# Pilot_Interface_005.net
KiCad netlist of a schematic drawn in EAGLE
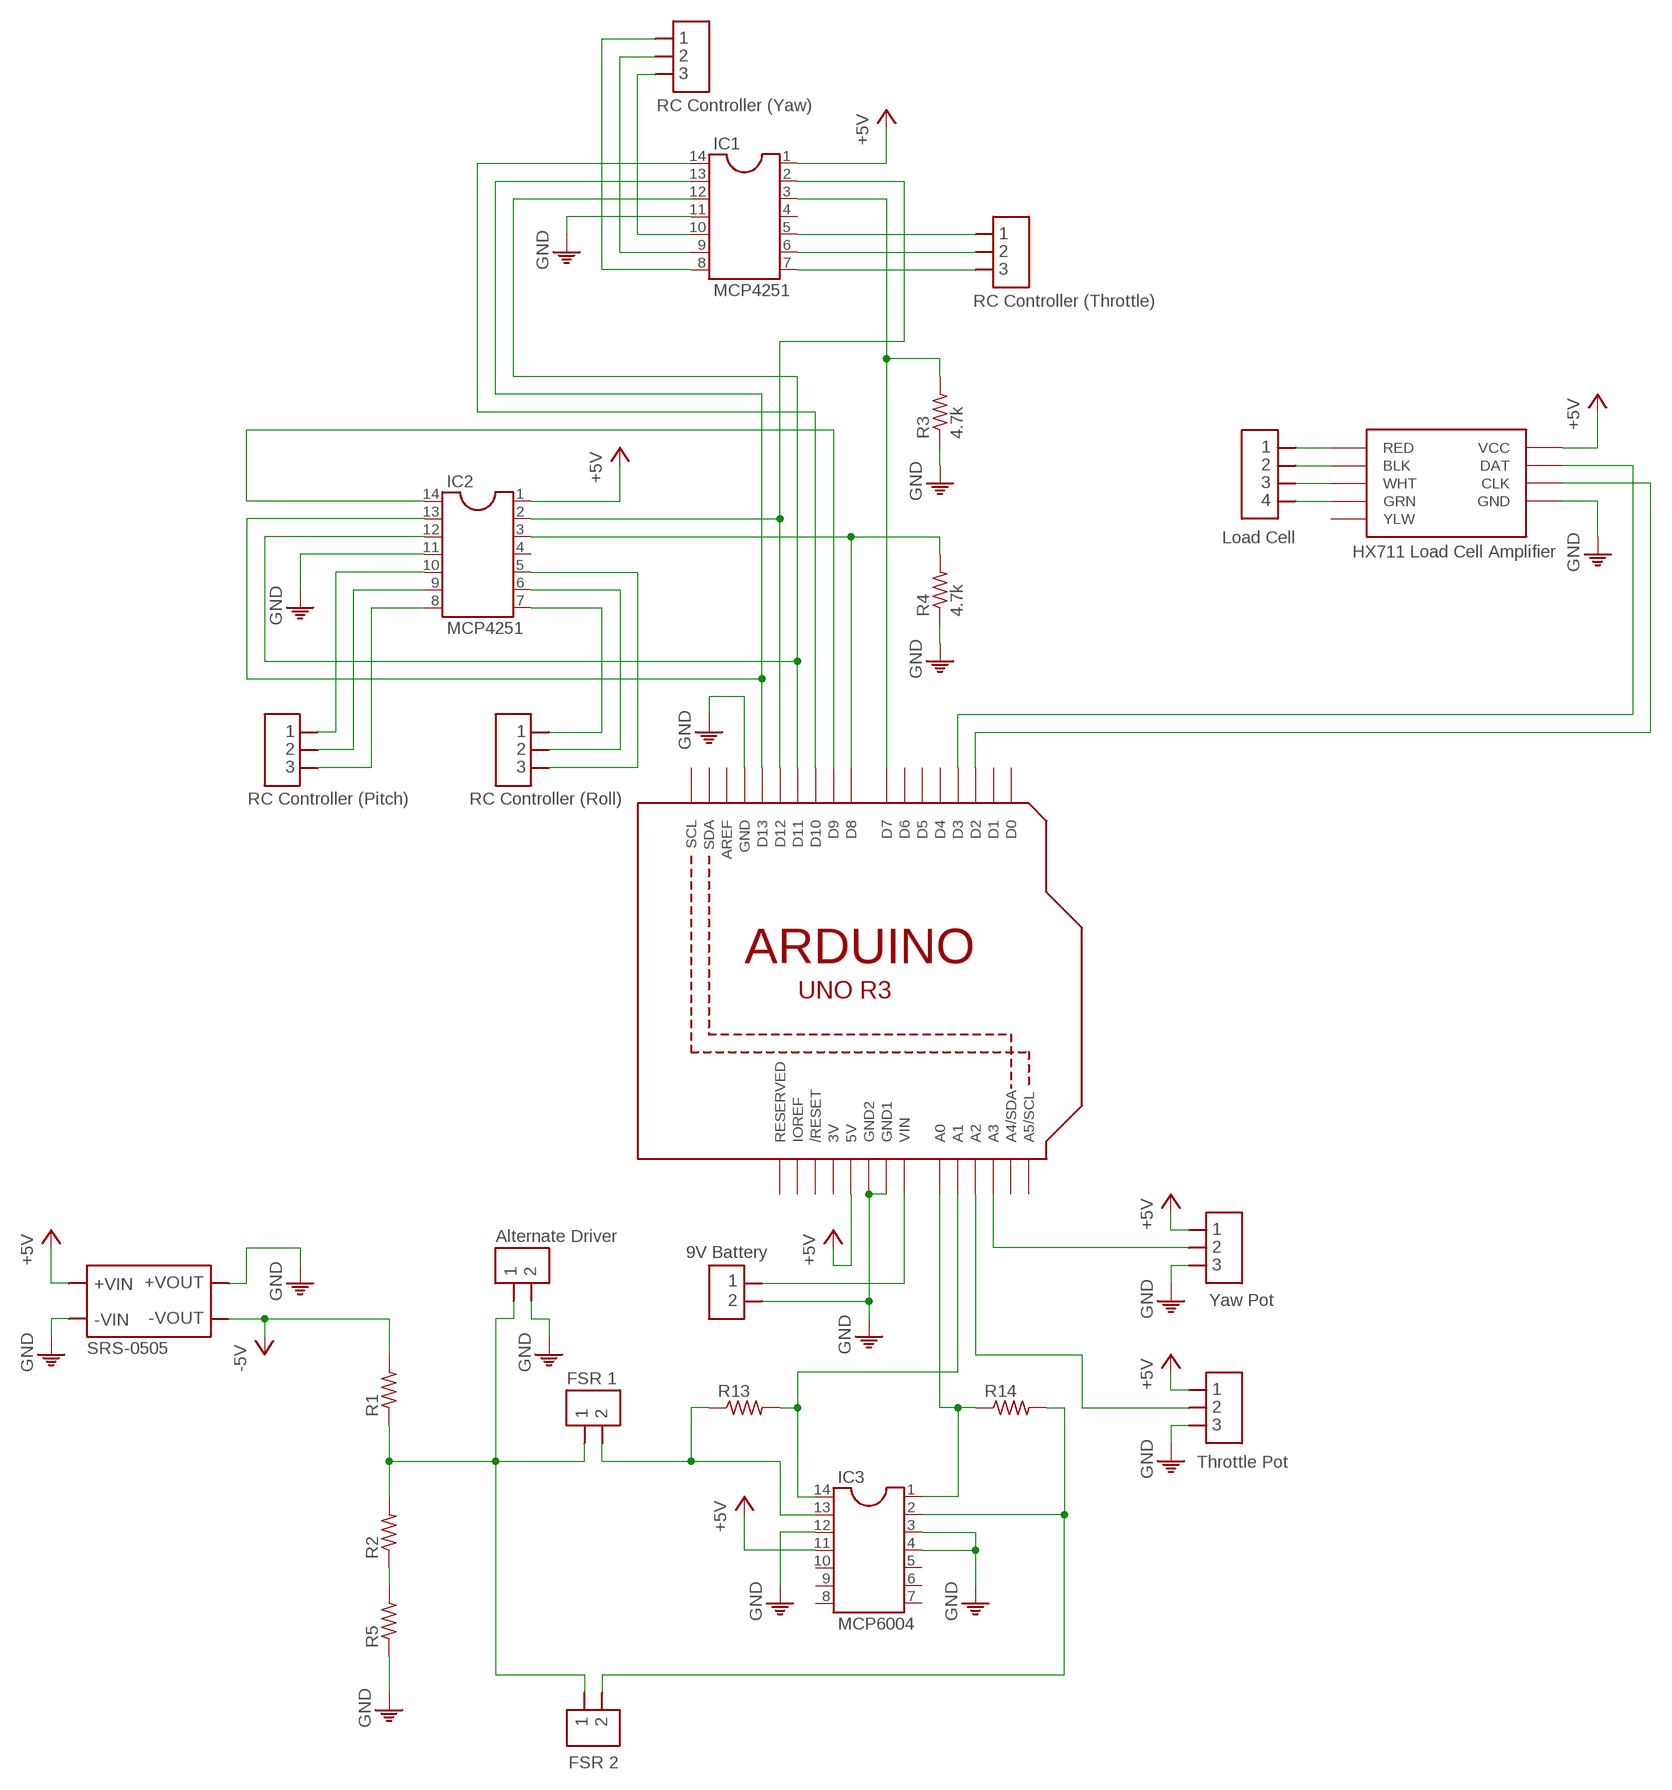
[diagram p0: schematic, sheet 1]

(export (version "E")
  (design (tool "Eeschema 10.0.6"))
  (components
    (comp (ref "IC1")
      (value "MCP4251")
      (footprint "eagle-import:DIL14")
      (libsource (lib "eagle-import") (part "DIL14"))
    )
    (comp (ref "IC2")
      (value "MCP4251")
      (footprint "eagle-import:DIL14")
      (libsource (lib "eagle-import") (part "DIL14"))
    )
    (comp (ref "IC3")
      (value "MCP6004")
      (footprint "eagle-import:DIL14")
      (libsource (lib "eagle-import") (part "DIL14"))
    )
    (comp (ref "R1")
      (value "R-US_0204/2V")
      (footprint "eagle-import:0204V")
      (libsource (lib "eagle-import") (part "R-US_0204/2V"))
    )
    (comp (ref "R2")
      (value "R-US_0204/2V")
      (footprint "eagle-import:0204V")
      (libsource (lib "eagle-import") (part "R-US_0204/2V"))
    )
    (comp (ref "R3")
      (value "4.7k")
      (footprint "eagle-import:0204V")
      (libsource (lib "eagle-import") (part "R-US_0204/2V"))
    )
    (comp (ref "R4")
      (value "4.7k")
      (footprint "eagle-import:0204V")
      (libsource (lib "eagle-import") (part "R-US_0204/2V"))
    )
    (comp (ref "R5")
      (value "R-US_0204/2V")
      (footprint "eagle-import:0204V")
      (libsource (lib "eagle-import") (part "R-US_0204/2V"))
    )
    (comp (ref "R13")
      (value "R-US_0204/2V")
      (footprint "eagle-import:0204V")
      (libsource (lib "eagle-import") (part "R-US_0204/2V"))
    )
    (comp (ref "R14")
      (value "R-US_0204/2V")
      (footprint "eagle-import:0204V")
      (libsource (lib "eagle-import") (part "R-US_0204/2V"))
    )
    (comp (ref "U$1")
      (value "HX711")
      (footprint "eagle-import:HX711")
      (libsource (lib "eagle-import") (part "HX711"))
    )
    (comp (ref "U$2")
      (value "PAD_3")
      (footprint "eagle-import:PAD_3")
      (libsource (lib "eagle-import") (part "PAD_3"))
    )
    (comp (ref "U$3")
      (value "PAD_3")
      (footprint "eagle-import:PAD_3")
      (libsource (lib "eagle-import") (part "PAD_3"))
    )
    (comp (ref "U$4")
      (value "PAD_2")
      (footprint "eagle-import:PAD_2")
      (libsource (lib "eagle-import") (part "PAD_2"))
    )
    (comp (ref "U$5")
      (value "PAD_2")
      (footprint "eagle-import:PAD_2")
      (libsource (lib "eagle-import") (part "PAD_2"))
    )
    (comp (ref "U$6")
      (value "PAD_3")
      (footprint "eagle-import:PAD_3")
      (libsource (lib "eagle-import") (part "PAD_3"))
    )
    (comp (ref "U$7")
      (value "PAD_3")
      (footprint "eagle-import:PAD_3")
      (libsource (lib "eagle-import") (part "PAD_3"))
    )
    (comp (ref "U$8")
      (value "PAD_4")
      (footprint "eagle-import:PAD_4")
      (libsource (lib "eagle-import") (part "PAD_4"))
    )
    (comp (ref "U$9")
      (value "SRS-0505")
      (footprint "eagle-import:SRS-0505")
      (libsource (lib "eagle-import") (part "SRS-0505"))
    )
    (comp (ref "U$10")
      (value "PAD_3")
      (footprint "eagle-import:PAD_3")
      (libsource (lib "eagle-import") (part "PAD_3"))
    )
    (comp (ref "U$11")
      (value "PAD_3")
      (footprint "eagle-import:PAD_3")
      (libsource (lib "eagle-import") (part "PAD_3"))
    )
    (comp (ref "U$12")
      (value "PAD_2")
      (footprint "eagle-import:PAD_2")
      (libsource (lib "eagle-import") (part "PAD_2"))
    )
    (comp (ref "U$13")
      (value "PAD_2")
      (footprint "eagle-import:PAD_2")
      (libsource (lib "eagle-import") (part "PAD_2"))
    )
    (comp (ref "U1")
      (value "ARDUINOR3")
      (footprint "eagle-import:ARDUINOR3")
      (libsource (lib "eagle-import") (part "ARDUINOR3"))
    )
  )
  (nets
    (net (code "1") (name "+5V") (class "Default")
      (node (ref "IC1") (pin "1") (pinfunction "14_1") (pintype "passive"))
      (node (ref "IC2") (pin "1") (pinfunction "14_1") (pintype "passive"))
      (node (ref "IC3") (pin "11") (pinfunction "4_11") (pintype "passive"))
      (node (ref "U$1") (pin "VCC") (pinfunction "VCC_VCC") (pintype "bidirectional"))
      (node (ref "U$6") (pin "P$1") (pinfunction "P$1_P$1") (pintype "bidirectional"))
      (node (ref "U$7") (pin "P$1") (pinfunction "P$1_P$1") (pintype "bidirectional"))
      (node (ref "U$9") (pin "P$1") (pinfunction "+VIN_P$1") (pintype "bidirectional"))
      (node (ref "U$9") (pin "P$16") (pinfunction "+VIN_P$16") (pintype "bidirectional"))
      (node (ref "U1") (pin "5V") (pinfunction "5V_5V") (pintype "power_in"))
    )
    (net (code "2") (name "-5V") (class "Default")
      (node (ref "R1") (pin "2") (pinfunction "2_2") (pintype "passive"))
      (node (ref "U$9") (pin "P$11") (pinfunction "-VOUT_P$11") (pintype "bidirectional"))
      (node (ref "U$9") (pin "P$6") (pinfunction "-VOUT_P$6") (pintype "bidirectional"))
    )
    (net (code "3") (name "/3V") (class "Default")
      (node (ref "U1") (pin "3V") (pinfunction "3V_3V") (pintype "power_in"))
    )
    (net (code "4") (name "GND") (class "Default")
      (node (ref "IC1") (pin "11") (pinfunction "4_11") (pintype "passive"))
      (node (ref "IC2") (pin "11") (pinfunction "4_11") (pintype "passive"))
      (node (ref "IC3") (pin "12") (pinfunction "3_12") (pintype "passive"))
      (node (ref "IC3") (pin "3") (pinfunction "12_3") (pintype "passive"))
      (node (ref "IC3") (pin "4") (pinfunction "11_4") (pintype "passive"))
      (node (ref "R3") (pin "1") (pinfunction "1_1") (pintype "passive"))
      (node (ref "R4") (pin "1") (pinfunction "1_1") (pintype "passive"))
      (node (ref "R5") (pin "1") (pinfunction "1_1") (pintype "passive"))
      (node (ref "U$1") (pin "GND") (pinfunction "GND_GND") (pintype "bidirectional"))
      (node (ref "U$12") (pin "P$2") (pinfunction "P$2_P$2") (pintype "bidirectional"))
      (node (ref "U$13") (pin "P$2") (pinfunction "P$2_P$2") (pintype "bidirectional"))
      (node (ref "U$6") (pin "P$3") (pinfunction "P$3_P$3") (pintype "bidirectional"))
      (node (ref "U$7") (pin "P$3") (pinfunction "P$3_P$3") (pintype "bidirectional"))
      (node (ref "U$9") (pin "P$10") (pinfunction "+VOUT_P$10") (pintype "bidirectional"))
      (node (ref "U$9") (pin "P$7") (pinfunction "+VOUT_P$7") (pintype "bidirectional"))
      (node (ref "U$9") (pin "P$8") (pinfunction "-VIN_P$8") (pintype "bidirectional"))
      (node (ref "U$9") (pin "P$9") (pinfunction "-VIN_P$9") (pintype "bidirectional"))
      (node (ref "U1") (pin "GND") (pinfunction "GND_GND") (pintype "power_in"))
      (node (ref "U1") (pin "GND1") (pinfunction "GND1_GND1") (pintype "power_in"))
      (node (ref "U1") (pin "GND2") (pinfunction "GND2_GND2") (pintype "power_in"))
    )
    (net (code "5") (name "Net-(IC1-1)") (class "Default")
      (node (ref "IC1") (pin "14") (pinfunction "1_14") (pintype "passive"))
      (node (ref "U1") (pin "D10") (pinfunction "D10_D10") (pintype "bidirectional"))
    )
    (net (code "6") (name "Net-(IC1-2)") (class "Default")
      (node (ref "IC1") (pin "13") (pinfunction "2_13") (pintype "passive"))
      (node (ref "IC2") (pin "13") (pinfunction "2_13") (pintype "passive"))
      (node (ref "U1") (pin "D13") (pinfunction "D13_D13") (pintype "bidirectional"))
    )
    (net (code "7") (name "Net-(IC1-3)") (class "Default")
      (node (ref "IC1") (pin "12") (pinfunction "3_12") (pintype "passive"))
      (node (ref "IC2") (pin "12") (pinfunction "3_12") (pintype "passive"))
      (node (ref "U1") (pin "D11") (pinfunction "D11_D11") (pintype "bidirectional"))
    )
    (net (code "8") (name "Net-(IC1-5)") (class "Default")
      (node (ref "IC1") (pin "10") (pinfunction "5_10") (pintype "passive"))
      (node (ref "U$2") (pin "P$3") (pinfunction "P$3_P$3") (pintype "bidirectional"))
    )
    (net (code "9") (name "Net-(IC1-6)") (class "Default")
      (node (ref "IC1") (pin "9") (pinfunction "6_9") (pintype "passive"))
      (node (ref "U$2") (pin "P$2") (pinfunction "P$2_P$2") (pintype "bidirectional"))
    )
    (net (code "10") (name "Net-(IC1-7)") (class "Default")
      (node (ref "IC1") (pin "8") (pinfunction "7_8") (pintype "passive"))
      (node (ref "U$2") (pin "P$1") (pinfunction "P$1_P$1") (pintype "bidirectional"))
    )
    (net (code "11") (name "Net-(IC1-8)") (class "Default")
      (node (ref "IC1") (pin "7") (pinfunction "8_7") (pintype "passive"))
      (node (ref "U$3") (pin "P$3") (pinfunction "P$3_P$3") (pintype "bidirectional"))
    )
    (net (code "12") (name "Net-(IC1-9)") (class "Default")
      (node (ref "IC1") (pin "6") (pinfunction "9_6") (pintype "passive"))
      (node (ref "U$3") (pin "P$2") (pinfunction "P$2_P$2") (pintype "bidirectional"))
    )
    (net (code "13") (name "Net-(IC1-10)") (class "Default")
      (node (ref "IC1") (pin "5") (pinfunction "10_5") (pintype "passive"))
      (node (ref "U$3") (pin "P$1") (pinfunction "P$1_P$1") (pintype "bidirectional"))
    )
    (net (code "14") (name "Net-(IC1-12)") (class "Default")
      (node (ref "IC1") (pin "3") (pinfunction "12_3") (pintype "passive"))
      (node (ref "R3") (pin "2") (pinfunction "2_2") (pintype "passive"))
      (node (ref "U1") (pin "D7") (pinfunction "D7_D7") (pintype "bidirectional"))
    )
    (net (code "15") (name "Net-(IC1-13)") (class "Default")
      (node (ref "IC1") (pin "2") (pinfunction "13_2") (pintype "passive"))
      (node (ref "IC2") (pin "2") (pinfunction "13_2") (pintype "passive"))
      (node (ref "U1") (pin "D12") (pinfunction "D12_D12") (pintype "bidirectional"))
    )
    (net (code "16") (name "Net-(IC2-1)") (class "Default")
      (node (ref "IC2") (pin "14") (pinfunction "1_14") (pintype "passive"))
      (node (ref "U1") (pin "D9") (pinfunction "D9_D9") (pintype "bidirectional"))
    )
    (net (code "17") (name "Net-(IC2-5)") (class "Default")
      (node (ref "IC2") (pin "10") (pinfunction "5_10") (pintype "passive"))
      (node (ref "U$10") (pin "P$1") (pinfunction "P$1_P$1") (pintype "bidirectional"))
    )
    (net (code "18") (name "Net-(IC2-6)") (class "Default")
      (node (ref "IC2") (pin "9") (pinfunction "6_9") (pintype "passive"))
      (node (ref "U$10") (pin "P$2") (pinfunction "P$2_P$2") (pintype "bidirectional"))
    )
    (net (code "19") (name "Net-(IC2-7)") (class "Default")
      (node (ref "IC2") (pin "8") (pinfunction "7_8") (pintype "passive"))
      (node (ref "U$10") (pin "P$3") (pinfunction "P$3_P$3") (pintype "bidirectional"))
    )
    (net (code "20") (name "Net-(IC2-8)") (class "Default")
      (node (ref "IC2") (pin "7") (pinfunction "8_7") (pintype "passive"))
      (node (ref "U$11") (pin "P$1") (pinfunction "P$1_P$1") (pintype "bidirectional"))
    )
    (net (code "21") (name "Net-(IC2-9)") (class "Default")
      (node (ref "IC2") (pin "6") (pinfunction "9_6") (pintype "passive"))
      (node (ref "U$11") (pin "P$2") (pinfunction "P$2_P$2") (pintype "bidirectional"))
    )
    (net (code "22") (name "Net-(IC2-10)") (class "Default")
      (node (ref "IC2") (pin "5") (pinfunction "10_5") (pintype "passive"))
      (node (ref "U$11") (pin "P$3") (pinfunction "P$3_P$3") (pintype "bidirectional"))
    )
    (net (code "23") (name "Net-(IC2-12)") (class "Default")
      (node (ref "IC2") (pin "3") (pinfunction "12_3") (pintype "passive"))
      (node (ref "R4") (pin "2") (pinfunction "2_2") (pintype "passive"))
      (node (ref "U1") (pin "D8") (pinfunction "D8_D8") (pintype "bidirectional"))
    )
    (net (code "24") (name "Net-(IC3-1)") (class "Default")
      (node (ref "IC3") (pin "14") (pinfunction "1_14") (pintype "passive"))
      (node (ref "R13") (pin "2") (pinfunction "2_2") (pintype "passive"))
      (node (ref "U1") (pin "A1") (pinfunction "A1_A1") (pintype "bidirectional"))
    )
    (net (code "25") (name "Net-(IC3-2)") (class "Default")
      (node (ref "IC3") (pin "13") (pinfunction "2_13") (pintype "passive"))
      (node (ref "R13") (pin "1") (pinfunction "1_1") (pintype "passive"))
      (node (ref "U$4") (pin "P$2") (pinfunction "P$2_P$2") (pintype "bidirectional"))
    )
    (net (code "26") (name "Net-(IC3-13)") (class "Default")
      (node (ref "IC3") (pin "2") (pinfunction "13_2") (pintype "passive"))
      (node (ref "R14") (pin "2") (pinfunction "2_2") (pintype "passive"))
      (node (ref "U$5") (pin "P$2") (pinfunction "P$2_P$2") (pintype "bidirectional"))
    )
    (net (code "27") (name "Net-(IC3-14)") (class "Default")
      (node (ref "IC3") (pin "1") (pinfunction "14_1") (pintype "passive"))
      (node (ref "R14") (pin "1") (pinfunction "1_1") (pintype "passive"))
      (node (ref "U1") (pin "A0") (pinfunction "A0_A0") (pintype "bidirectional"))
    )
    (net (code "28") (name "Net-(R1-Pad1)") (class "Default")
      (node (ref "R1") (pin "1") (pinfunction "1_1") (pintype "passive"))
      (node (ref "R2") (pin "2") (pinfunction "2_2") (pintype "passive"))
      (node (ref "U$12") (pin "P$1") (pinfunction "P$1_P$1") (pintype "bidirectional"))
      (node (ref "U$4") (pin "P$1") (pinfunction "P$1_P$1") (pintype "bidirectional"))
      (node (ref "U$5") (pin "P$1") (pinfunction "P$1_P$1") (pintype "bidirectional"))
    )
    (net (code "29") (name "Net-(R2-Pad1)") (class "Default")
      (node (ref "R2") (pin "1") (pinfunction "1_1") (pintype "passive"))
      (node (ref "R5") (pin "2") (pinfunction "2_2") (pintype "passive"))
    )
    (net (code "30") (name "Net-(U$1-PadBLK)") (class "Default")
      (node (ref "U$1") (pin "BLK") (pinfunction "BLK_BLK") (pintype "bidirectional"))
      (node (ref "U$8") (pin "P$2") (pinfunction "P$2_P$2") (pintype "bidirectional"))
    )
    (net (code "31") (name "Net-(U$1-PadCLK)") (class "Default")
      (node (ref "U$1") (pin "CLK") (pinfunction "CLK_CLK") (pintype "bidirectional"))
      (node (ref "U1") (pin "D2") (pinfunction "D2_D2") (pintype "bidirectional"))
    )
    (net (code "32") (name "Net-(U$1-PadDAT)") (class "Default")
      (node (ref "U$1") (pin "DAT") (pinfunction "DAT_DAT") (pintype "bidirectional"))
      (node (ref "U1") (pin "D3") (pinfunction "D3_D3") (pintype "bidirectional"))
    )
    (net (code "33") (name "Net-(U$1-PadGRN)") (class "Default")
      (node (ref "U$1") (pin "GRN") (pinfunction "GRN_GRN") (pintype "bidirectional"))
      (node (ref "U$8") (pin "P$4") (pinfunction "P$4_P$4") (pintype "bidirectional"))
    )
    (net (code "34") (name "Net-(U$1-PadRED)") (class "Default")
      (node (ref "U$1") (pin "RED") (pinfunction "RED_RED") (pintype "bidirectional"))
      (node (ref "U$8") (pin "P$1") (pinfunction "P$1_P$1") (pintype "bidirectional"))
    )
    (net (code "35") (name "Net-(U$1-PadWHT)") (class "Default")
      (node (ref "U$1") (pin "WHT") (pinfunction "WHT_WHT") (pintype "bidirectional"))
      (node (ref "U$8") (pin "P$3") (pinfunction "P$3_P$3") (pintype "bidirectional"))
    )
    (net (code "36") (name "Net-(U$6-PadP$2)") (class "Default")
      (node (ref "U$6") (pin "P$2") (pinfunction "P$2_P$2") (pintype "bidirectional"))
      (node (ref "U1") (pin "A3") (pinfunction "A3_A3") (pintype "bidirectional"))
    )
    (net (code "37") (name "Net-(U$7-PadP$2)") (class "Default")
      (node (ref "U$7") (pin "P$2") (pinfunction "P$2_P$2") (pintype "bidirectional"))
      (node (ref "U1") (pin "A2") (pinfunction "A2_A2") (pintype "bidirectional"))
    )
    (net (code "38") (name "Net-(U$13-PadP$1)") (class "Default")
      (node (ref "U$13") (pin "P$1") (pinfunction "P$1_P$1") (pintype "bidirectional"))
      (node (ref "U1") (pin "VIN") (pinfunction "VIN_VIN") (pintype "power_in"))
    )
    (net (code "39") (name "unconnected-(IC1-11-Pad4)") (class "Default")
      (node (ref "IC1") (pin "4") (pinfunction "11_4") (pintype "passive"))
    )
    (net (code "40") (name "unconnected-(IC2-11-Pad4)") (class "Default")
      (node (ref "IC2") (pin "4") (pinfunction "11_4") (pintype "passive"))
    )
    (net (code "41") (name "unconnected-(IC3-5-Pad10)") (class "Default")
      (node (ref "IC3") (pin "10") (pinfunction "5_10") (pintype "passive"))
    )
    (net (code "42") (name "unconnected-(IC3-6-Pad9)") (class "Default")
      (node (ref "IC3") (pin "9") (pinfunction "6_9") (pintype "passive"))
    )
    (net (code "43") (name "unconnected-(IC3-7-Pad8)") (class "Default")
      (node (ref "IC3") (pin "8") (pinfunction "7_8") (pintype "passive"))
    )
    (net (code "44") (name "unconnected-(IC3-8-Pad7)") (class "Default")
      (node (ref "IC3") (pin "7") (pinfunction "8_7") (pintype "passive"))
    )
    (net (code "45") (name "unconnected-(IC3-9-Pad6)") (class "Default")
      (node (ref "IC3") (pin "6") (pinfunction "9_6") (pintype "passive"))
    )
    (net (code "46") (name "unconnected-(IC3-10-Pad5)") (class "Default")
      (node (ref "IC3") (pin "5") (pinfunction "10_5") (pintype "passive"))
    )
    (net (code "47") (name "unconnected-(U$1-PadYLW)") (class "Default")
      (node (ref "U$1") (pin "YLW") (pinfunction "YLW_YLW") (pintype "bidirectional"))
    )
    (net (code "48") (name "unconnected-(U1-A4{slash}SDA-PadA4)") (class "Default")
      (node (ref "U1") (pin "A4") (pinfunction "A4/SDA_A4") (pintype "bidirectional"))
    )
    (net (code "49") (name "unconnected-(U1-A5{slash}SCL-PadA5)") (class "Default")
      (node (ref "U1") (pin "A5") (pinfunction "A5/SCL_A5") (pintype "bidirectional"))
    )
    (net (code "50") (name "unconnected-(U1-PadAREF)") (class "Default")
      (node (ref "U1") (pin "AREF") (pinfunction "AREF_AREF") (pintype "bidirectional"))
    )
    (net (code "51") (name "unconnected-(U1-PadD0)") (class "Default")
      (node (ref "U1") (pin "D0") (pinfunction "D0_D0") (pintype "bidirectional"))
    )
    (net (code "52") (name "unconnected-(U1-PadD1)") (class "Default")
      (node (ref "U1") (pin "D1") (pinfunction "D1_D1") (pintype "bidirectional"))
    )
    (net (code "53") (name "unconnected-(U1-PadD4)") (class "Default")
      (node (ref "U1") (pin "D4") (pinfunction "D4_D4") (pintype "bidirectional"))
    )
    (net (code "54") (name "unconnected-(U1-PadD5)") (class "Default")
      (node (ref "U1") (pin "D5") (pinfunction "D5_D5") (pintype "bidirectional"))
    )
    (net (code "55") (name "unconnected-(U1-PadD6)") (class "Default")
      (node (ref "U1") (pin "D6") (pinfunction "D6_D6") (pintype "bidirectional"))
    )
    (net (code "56") (name "unconnected-(U1-PadIOREF)") (class "Default")
      (node (ref "U1") (pin "IOREF") (pinfunction "IOREF_IOREF") (pintype "output"))
    )
    (net (code "57") (name "unconnected-(U1-PadRESERVED)") (class "Default")
      (node (ref "U1") (pin "RESERVED") (pinfunction "RESERVED_RESERVED") (pintype "no_connect"))
    )
    (net (code "58") (name "unconnected-(U1-PadSCL)") (class "Default")
      (node (ref "U1") (pin "SCL") (pinfunction "SCL_SCL") (pintype "bidirectional"))
    )
    (net (code "59") (name "unconnected-(U1-PadSDA)") (class "Default")
      (node (ref "U1") (pin "SDA") (pinfunction "SDA_SDA") (pintype "bidirectional"))
    )
    (net (code "60") (name "unconnected-(U1-{slash}RESET-PadRESET)") (class "Default")
      (node (ref "U1") (pin "RESET") (pinfunction "/RESET_RESET") (pintype "bidirectional"))
    )
  )
)
